# DinoCalc_3v0.net
KiCad netlist of a schematic drawn in EAGLE
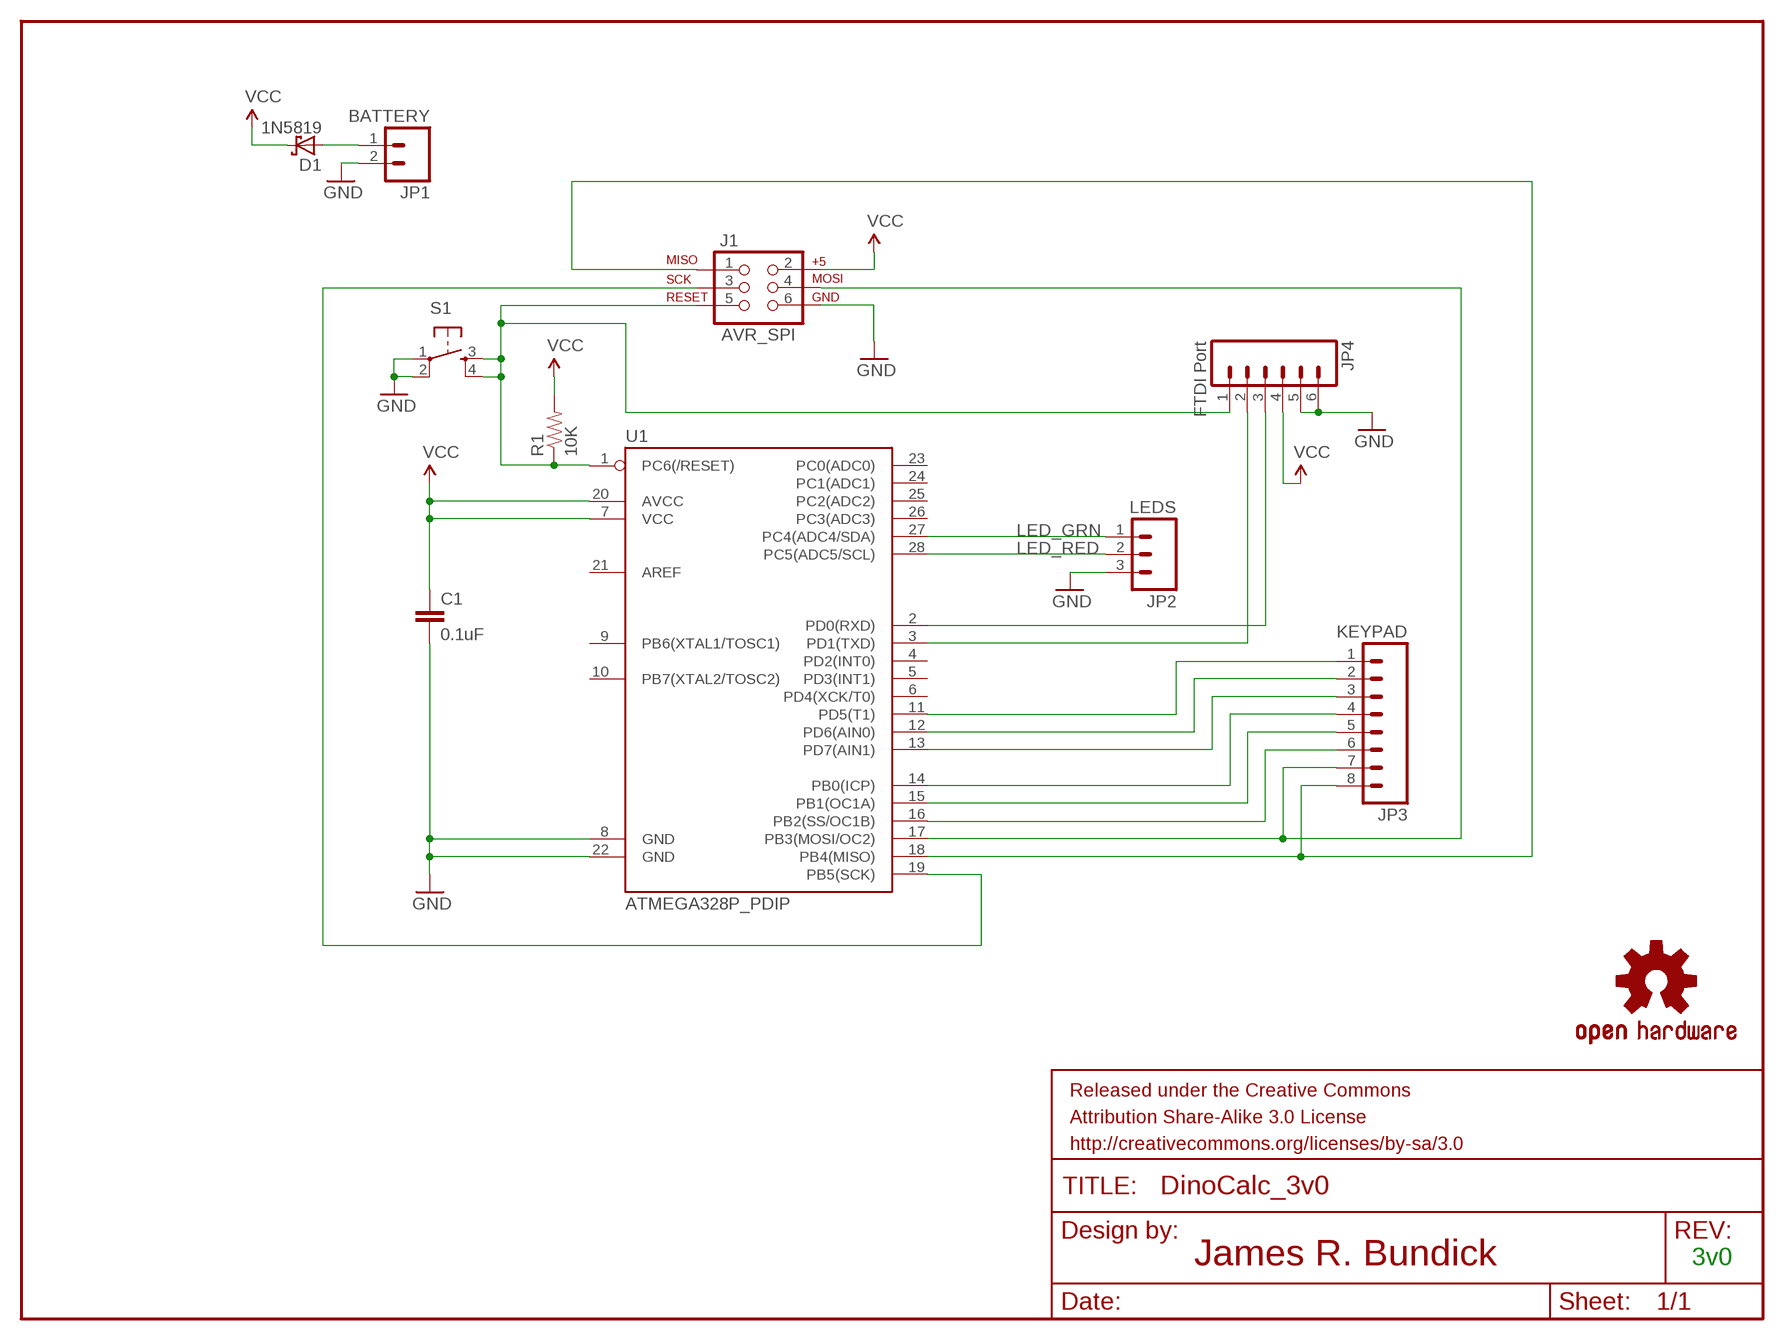
[diagram p0: schematic, sheet 1]

(export (version "E")
  (design (tool "Eeschema 10.0.6"))
  (components
    (comp (ref "C1")
      (value "0.1uF")
      (footprint "eagle-import:CAP-PTH-SMALL")
      (libsource (lib "eagle-import") (part "CAPPTH"))
    )
    (comp (ref "D1")
      (value "1N5819")
      (footprint "eagle-import:CB417-15")
      (libsource (lib "eagle-import") (part "SCHOTTKY-DIODECB417-15"))
    )
    (comp (ref "FRAME1")
      (value "FRAME-LETTER")
      (footprint "eagle-import:CREATIVE_COMMONS")
      (libsource (lib "eagle-import") (part "FRAME-LETTER"))
    )
    (comp (ref "J1")
      (value "AVR_SPI")
      (footprint "eagle-import:2X3_OFFSET")
      (libsource (lib "eagle-import") (part "AVR_SPI_PRG_6OFFSET_PADS"))
    )
    (comp (ref "JP1")
      (value "BATTERY")
      (footprint "eagle-import:1X02")
      (libsource (lib "eagle-import") (part "M02PTH"))
    )
    (comp (ref "JP2")
      (value "LEDS")
      (footprint "eagle-import:1X03")
      (libsource (lib "eagle-import") (part "M03PTH"))
    )
    (comp (ref "JP3")
      (value "KEYPAD")
      (footprint "eagle-import:1X08")
      (libsource (lib "eagle-import") (part "M081X08"))
    )
    (comp (ref "JP4")
      (value "FTDI Port")
      (footprint "eagle-import:1X06_LONGPADS")
      (libsource (lib "eagle-import") (part "M06LONGPADS"))
    )
    (comp (ref "LOGO1")
      (value "OSHW-LOGOL")
      (footprint "eagle-import:OSHW-LOGO-L")
      (libsource (lib "eagle-import") (part "OSHW-LOGOL"))
    )
    (comp (ref "R1")
      (value "10K")
      (footprint "eagle-import:AXIAL-0.4")
      (libsource (lib "eagle-import") (part "RESISTORPTH-1/4W"))
    )
    (comp (ref "S1")
      (value "TAC_SWITCHPTH")
      (footprint "eagle-import:TACTILE-PTH")
      (libsource (lib "eagle-import") (part "TAC_SWITCHPTH"))
    )
    (comp (ref "U1")
      (value "ATMEGA328P_PDIP")
      (footprint "eagle-import:DIL28-3")
      (libsource (lib "eagle-import") (part "ATMEGA328P_PDIP"))
    )
  )
  (nets
    (net (code "1") (name "/LED_GRN") (class "Default")
      (node (ref "JP2") (pin "1") (pinfunction "1_1") (pintype "passive"))
      (node (ref "U1") (pin "27") (pinfunction "PC4(ADC4/SDA)_27") (pintype "bidirectional"))
    )
    (net (code "2") (name "/LED_RED") (class "Default")
      (node (ref "JP2") (pin "2") (pinfunction "2_2") (pintype "passive"))
      (node (ref "U1") (pin "28") (pinfunction "PC5(ADC5/SCL)_28") (pintype "bidirectional"))
    )
    (net (code "3") (name "GND") (class "Default")
      (node (ref "C1") (pin "2") (pinfunction "2_2") (pintype "passive"))
      (node (ref "J1") (pin "6") (pinfunction "6_6") (pintype "passive"))
      (node (ref "JP1") (pin "2") (pinfunction "2_2") (pintype "passive"))
      (node (ref "JP2") (pin "3") (pinfunction "3_3") (pintype "passive"))
      (node (ref "JP4") (pin "5") (pinfunction "5_5") (pintype "passive"))
      (node (ref "JP4") (pin "6") (pinfunction "6_6") (pintype "passive"))
      (node (ref "S1") (pin "1") (pinfunction "1_1") (pintype "passive"))
      (node (ref "S1") (pin "2") (pinfunction "2_2") (pintype "passive"))
      (node (ref "U1") (pin "22") (pinfunction "GND_22") (pintype "bidirectional"))
      (node (ref "U1") (pin "8") (pinfunction "GND_8") (pintype "bidirectional"))
    )
    (net (code "4") (name "Net-(D1-PadA)") (class "Default")
      (node (ref "D1") (pin "A") (pinfunction "A_A") (pintype "passive"))
      (node (ref "JP1") (pin "1") (pinfunction "1_1") (pintype "passive"))
    )
    (net (code "5") (name "Net-(R1-1)") (class "Default")
      (node (ref "J1") (pin "5") (pinfunction "5_5") (pintype "passive"))
      (node (ref "JP4") (pin "1") (pinfunction "1_1") (pintype "passive"))
      (node (ref "R1") (pin "P$1") (pinfunction "1_P$1") (pintype "passive"))
      (node (ref "S1") (pin "3") (pinfunction "3_3") (pintype "passive"))
      (node (ref "S1") (pin "4") (pinfunction "4_4") (pintype "passive"))
      (node (ref "U1") (pin "1") (pinfunction "PC6(/RESET)_1") (pintype "bidirectional"))
    )
    (net (code "6") (name "Net-(U1-PB0(ICP))") (class "Default")
      (node (ref "JP3") (pin "4") (pinfunction "4_4") (pintype "passive"))
      (node (ref "U1") (pin "14") (pinfunction "PB0(ICP)_14") (pintype "bidirectional"))
    )
    (net (code "7") (name "Net-(U1-PB1(OC1A))") (class "Default")
      (node (ref "JP3") (pin "5") (pinfunction "5_5") (pintype "passive"))
      (node (ref "U1") (pin "15") (pinfunction "PB1(OC1A)_15") (pintype "bidirectional"))
    )
    (net (code "8") (name "Net-(U1-PB2(SS{slash}OC1B))") (class "Default")
      (node (ref "JP3") (pin "6") (pinfunction "6_6") (pintype "passive"))
      (node (ref "U1") (pin "16") (pinfunction "PB2(SS/OC1B)_16") (pintype "bidirectional"))
    )
    (net (code "9") (name "Net-(U1-PB3(MOSI{slash}OC2))") (class "Default")
      (node (ref "J1") (pin "4") (pinfunction "4_4") (pintype "passive"))
      (node (ref "JP3") (pin "7") (pinfunction "7_7") (pintype "passive"))
      (node (ref "U1") (pin "17") (pinfunction "PB3(MOSI/OC2)_17") (pintype "bidirectional"))
    )
    (net (code "10") (name "Net-(U1-PB4(MISO))") (class "Default")
      (node (ref "J1") (pin "1") (pinfunction "1_1") (pintype "passive"))
      (node (ref "JP3") (pin "8") (pinfunction "8_8") (pintype "passive"))
      (node (ref "U1") (pin "18") (pinfunction "PB4(MISO)_18") (pintype "bidirectional"))
    )
    (net (code "11") (name "Net-(U1-PB5(SCK))") (class "Default")
      (node (ref "J1") (pin "3") (pinfunction "3_3") (pintype "passive"))
      (node (ref "U1") (pin "19") (pinfunction "PB5(SCK)_19") (pintype "bidirectional"))
    )
    (net (code "12") (name "Net-(U1-PD0(RXD))") (class "Default")
      (node (ref "JP4") (pin "3") (pinfunction "3_3") (pintype "passive"))
      (node (ref "U1") (pin "2") (pinfunction "PD0(RXD)_2") (pintype "bidirectional"))
    )
    (net (code "13") (name "Net-(U1-PD1(TXD))") (class "Default")
      (node (ref "JP4") (pin "2") (pinfunction "2_2") (pintype "passive"))
      (node (ref "U1") (pin "3") (pinfunction "PD1(TXD)_3") (pintype "bidirectional"))
    )
    (net (code "14") (name "Net-(U1-PD5(T1))") (class "Default")
      (node (ref "JP3") (pin "1") (pinfunction "1_1") (pintype "passive"))
      (node (ref "U1") (pin "11") (pinfunction "PD5(T1)_11") (pintype "bidirectional"))
    )
    (net (code "15") (name "Net-(U1-PD6(AIN0))") (class "Default")
      (node (ref "JP3") (pin "2") (pinfunction "2_2") (pintype "passive"))
      (node (ref "U1") (pin "12") (pinfunction "PD6(AIN0)_12") (pintype "bidirectional"))
    )
    (net (code "16") (name "Net-(U1-PD7(AIN1))") (class "Default")
      (node (ref "JP3") (pin "3") (pinfunction "3_3") (pintype "passive"))
      (node (ref "U1") (pin "13") (pinfunction "PD7(AIN1)_13") (pintype "bidirectional"))
    )
    (net (code "17") (name "VCC") (class "Default")
      (node (ref "C1") (pin "1") (pinfunction "1_1") (pintype "passive"))
      (node (ref "D1") (pin "C") (pinfunction "C_C") (pintype "passive"))
      (node (ref "J1") (pin "2") (pinfunction "2_2") (pintype "passive"))
      (node (ref "JP4") (pin "4") (pinfunction "4_4") (pintype "passive"))
      (node (ref "R1") (pin "P$2") (pinfunction "2_P$2") (pintype "passive"))
      (node (ref "U1") (pin "20") (pinfunction "AVCC_20") (pintype "bidirectional"))
      (node (ref "U1") (pin "7") (pinfunction "VCC_7") (pintype "bidirectional"))
    )
    (net (code "18") (name "unconnected-(U1-AREF-Pad21)") (class "Default")
      (node (ref "U1") (pin "21") (pinfunction "AREF_21") (pintype "bidirectional"))
    )
    (net (code "19") (name "unconnected-(U1-PB6(XTAL1{slash}TOSC1)-Pad9)") (class "Default")
      (node (ref "U1") (pin "9") (pinfunction "PB6(XTAL1/TOSC1)_9") (pintype "bidirectional"))
    )
    (net (code "20") (name "unconnected-(U1-PB7(XTAL2{slash}TOSC2)-Pad10)") (class "Default")
      (node (ref "U1") (pin "10") (pinfunction "PB7(XTAL2/TOSC2)_10") (pintype "bidirectional"))
    )
    (net (code "21") (name "unconnected-(U1-PC0(ADC0)-Pad23)") (class "Default")
      (node (ref "U1") (pin "23") (pinfunction "PC0(ADC0)_23") (pintype "bidirectional"))
    )
    (net (code "22") (name "unconnected-(U1-PC1(ADC1)-Pad24)") (class "Default")
      (node (ref "U1") (pin "24") (pinfunction "PC1(ADC1)_24") (pintype "bidirectional"))
    )
    (net (code "23") (name "unconnected-(U1-PC2(ADC2)-Pad25)") (class "Default")
      (node (ref "U1") (pin "25") (pinfunction "PC2(ADC2)_25") (pintype "bidirectional"))
    )
    (net (code "24") (name "unconnected-(U1-PC3(ADC3)-Pad26)") (class "Default")
      (node (ref "U1") (pin "26") (pinfunction "PC3(ADC3)_26") (pintype "bidirectional"))
    )
    (net (code "25") (name "unconnected-(U1-PD2(INT0)-Pad4)") (class "Default")
      (node (ref "U1") (pin "4") (pinfunction "PD2(INT0)_4") (pintype "bidirectional"))
    )
    (net (code "26") (name "unconnected-(U1-PD3(INT1)-Pad5)") (class "Default")
      (node (ref "U1") (pin "5") (pinfunction "PD3(INT1)_5") (pintype "bidirectional"))
    )
    (net (code "27") (name "unconnected-(U1-PD4(XCK{slash}T0)-Pad6)") (class "Default")
      (node (ref "U1") (pin "6") (pinfunction "PD4(XCK/T0)_6") (pintype "bidirectional"))
    )
  )
)
